# PWM.net
KiCad netlist of a schematic drawn in Altium Designer
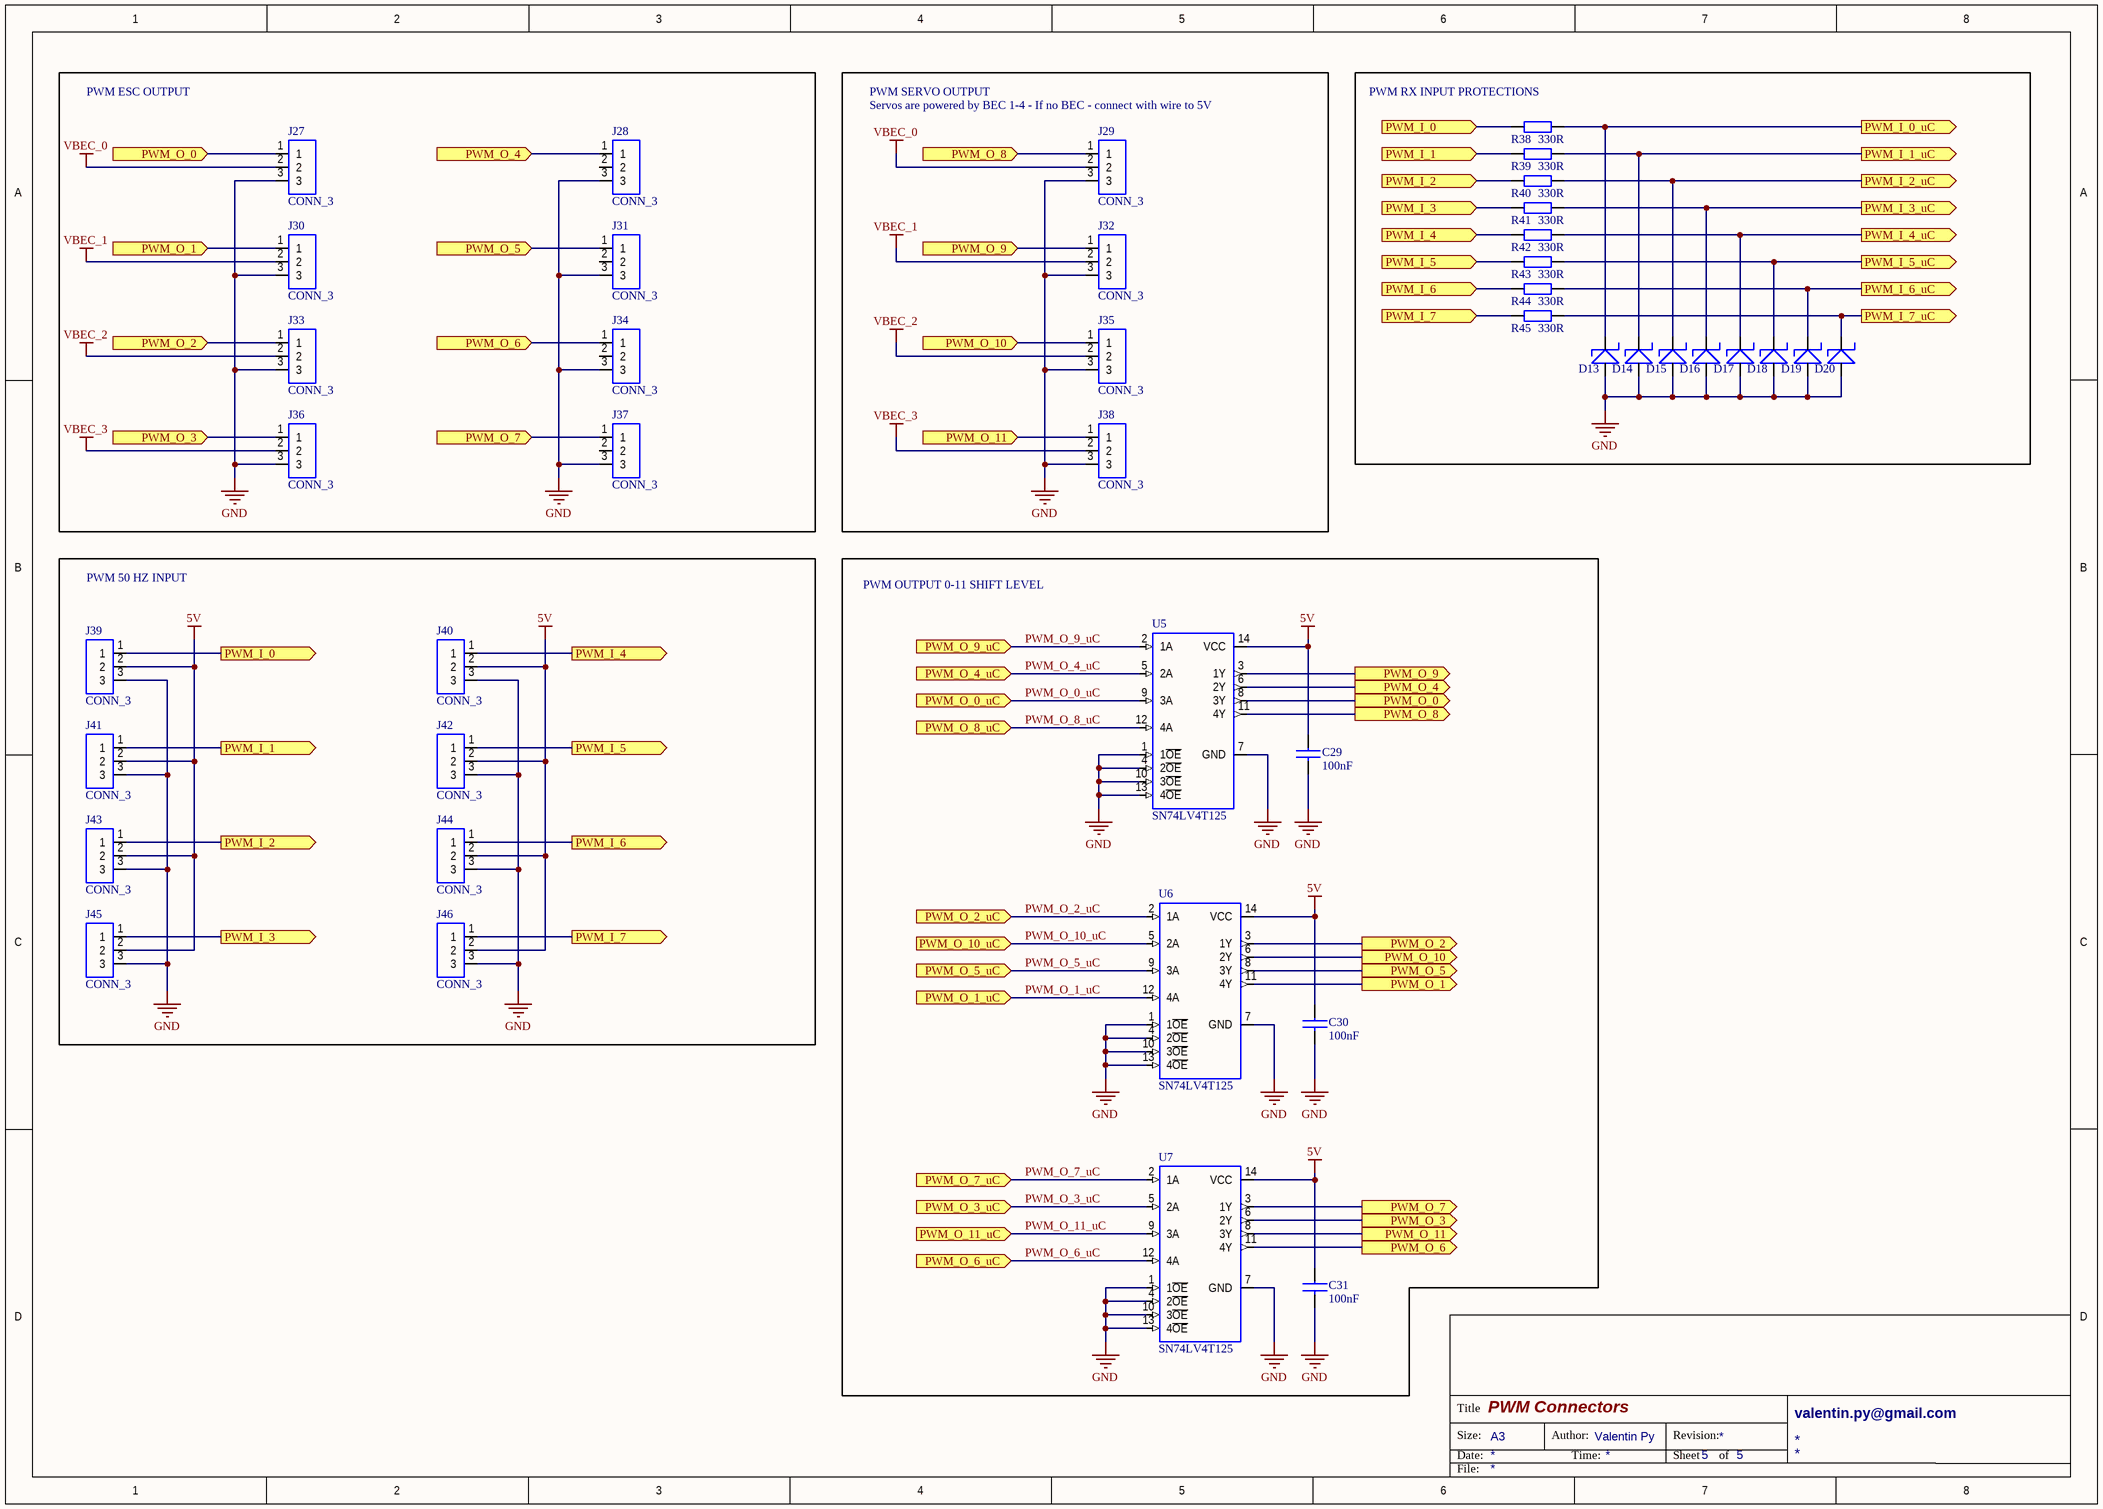
[diagram p0: PWM.SchDoc]

(export (version "E")
  (design (tool "Eeschema 10.0.6"))
  (components
    (comp (ref "C29")
      (value "100nF")
      (footprint "080503")
      (description "CAP CER 0.1UF 25V 10% X7R 0805")
      (libsource (lib "EISI") (part "CAPA"))
    )
    (comp (ref "C30")
      (value "100nF")
      (footprint "080503")
      (description "CAP CER 0.1UF 25V 10% X7R 0805")
      (libsource (lib "EISI") (part "CAPA"))
    )
    (comp (ref "C31")
      (value "100nF")
      (footprint "080503")
      (description "CAP CER 0.1UF 25V 10% X7R 0805")
      (libsource (lib "EISI") (part "CAPA"))
    )
    (comp (ref "D13")
      (value "TVS DIODE 3.3V")
      (footprint "SOD-523")
      (description "TVS DIODE 3.3VWM 8VC SOD523")
      (libsource (lib "PalIncTest") (part "Zener"))
    )
    (comp (ref "D14")
      (value "TVS DIODE 3.3V")
      (footprint "SOD-523")
      (description "TVS DIODE 3.3VWM 8VC SOD523")
      (libsource (lib "PalIncTest") (part "Zener"))
    )
    (comp (ref "D15")
      (value "TVS DIODE 3.3V")
      (footprint "SOD-523")
      (description "TVS DIODE 3.3VWM 8VC SOD523")
      (libsource (lib "PalIncTest") (part "Zener"))
    )
    (comp (ref "D16")
      (value "TVS DIODE 3.3V")
      (footprint "SOD-523")
      (description "TVS DIODE 3.3VWM 8VC SOD523")
      (libsource (lib "PalIncTest") (part "Zener"))
    )
    (comp (ref "D17")
      (value "TVS DIODE 3.3V")
      (footprint "SOD-523")
      (description "TVS DIODE 3.3VWM 8VC SOD523")
      (libsource (lib "PalIncTest") (part "Zener"))
    )
    (comp (ref "D18")
      (value "TVS DIODE 3.3V")
      (footprint "SOD-523")
      (description "TVS DIODE 3.3VWM 8VC SOD523")
      (libsource (lib "PalIncTest") (part "Zener"))
    )
    (comp (ref "D19")
      (value "TVS DIODE 3.3V")
      (footprint "SOD-523")
      (description "TVS DIODE 3.3VWM 8VC SOD523")
      (libsource (lib "PalIncTest") (part "Zener"))
    )
    (comp (ref "D20")
      (value "TVS DIODE 3.3V")
      (footprint "SOD-523")
      (description "TVS DIODE 3.3VWM 8VC SOD523")
      (libsource (lib "PalIncTest") (part "Zener"))
    )
    (comp (ref "J27")
      (value "CONN_3")
      (footprint "640454-3")
      (description "CONN HEADER 2.54mm 3")
      (libsource (lib "Aeroval") (part "CONN_3"))
    )
    (comp (ref "J28")
      (value "CONN_3")
      (footprint "640454-3")
      (description "CONN HEADER 2.54mm 3")
      (libsource (lib "Aeroval") (part "CONN_3"))
    )
    (comp (ref "J29")
      (value "CONN_3")
      (footprint "640454-3")
      (description "CONN HEADER 2.54mm 3")
      (libsource (lib "Aeroval") (part "CONN_3"))
    )
    (comp (ref "J30")
      (value "CONN_3")
      (footprint "640454-3")
      (description "CONN HEADER 2.54mm 3")
      (libsource (lib "Aeroval") (part "CONN_3"))
    )
    (comp (ref "J31")
      (value "CONN_3")
      (footprint "640454-3")
      (description "CONN HEADER 2.54mm 3")
      (libsource (lib "Aeroval") (part "CONN_3"))
    )
    (comp (ref "J32")
      (value "CONN_3")
      (footprint "640454-3")
      (description "CONN HEADER 2.54mm 3")
      (libsource (lib "Aeroval") (part "CONN_3"))
    )
    (comp (ref "J33")
      (value "CONN_3")
      (footprint "640454-3")
      (description "CONN HEADER 2.54mm 3")
      (libsource (lib "Aeroval") (part "CONN_3"))
    )
    (comp (ref "J34")
      (value "CONN_3")
      (footprint "640454-3")
      (description "CONN HEADER 2.54mm 3")
      (libsource (lib "Aeroval") (part "CONN_3"))
    )
    (comp (ref "J35")
      (value "CONN_3")
      (footprint "640454-3")
      (description "CONN HEADER 2.54mm 3")
      (libsource (lib "Aeroval") (part "CONN_3"))
    )
    (comp (ref "J36")
      (value "CONN_3")
      (footprint "640454-3")
      (description "CONN HEADER 2.54mm 3")
      (libsource (lib "Aeroval") (part "CONN_3"))
    )
    (comp (ref "J37")
      (value "CONN_3")
      (footprint "640454-3")
      (description "CONN HEADER 2.54mm 3")
      (libsource (lib "Aeroval") (part "CONN_3"))
    )
    (comp (ref "J38")
      (value "CONN_3")
      (footprint "640454-3")
      (description "CONN HEADER 2.54mm 3")
      (libsource (lib "Aeroval") (part "CONN_3"))
    )
    (comp (ref "J39")
      (value "CONN_3")
      (footprint "640454-3")
      (description "CONN HEADER 2.54mm 3")
      (libsource (lib "Aeroval") (part "CONN_3"))
    )
    (comp (ref "J40")
      (value "CONN_3")
      (footprint "640454-3")
      (description "CONN HEADER 2.54mm 3")
      (libsource (lib "Aeroval") (part "CONN_3"))
    )
    (comp (ref "J41")
      (value "CONN_3")
      (footprint "640454-3")
      (description "CONN HEADER 2.54mm 3")
      (libsource (lib "Aeroval") (part "CONN_3"))
    )
    (comp (ref "J42")
      (value "CONN_3")
      (footprint "640454-3")
      (description "CONN HEADER 2.54mm 3")
      (libsource (lib "Aeroval") (part "CONN_3"))
    )
    (comp (ref "J43")
      (value "CONN_3")
      (footprint "640454-3")
      (description "CONN HEADER 2.54mm 3")
      (libsource (lib "Aeroval") (part "CONN_3"))
    )
    (comp (ref "J44")
      (value "CONN_3")
      (footprint "640454-3")
      (description "CONN HEADER 2.54mm 3")
      (libsource (lib "Aeroval") (part "CONN_3"))
    )
    (comp (ref "J45")
      (value "CONN_3")
      (footprint "640454-3")
      (description "CONN HEADER 2.54mm 3")
      (libsource (lib "Aeroval") (part "CONN_3"))
    )
    (comp (ref "J46")
      (value "CONN_3")
      (footprint "640454-3")
      (description "CONN HEADER 2.54mm 3")
      (libsource (lib "Aeroval") (part "CONN_3"))
    )
    (comp (ref "R38")
      (value "330R")
      (footprint "060301")
      (description "RES 330R 0805")
      (libsource (lib "EISI") (part "RES"))
    )
    (comp (ref "R39")
      (value "330R")
      (footprint "060301")
      (description "RES 330R 0805")
      (libsource (lib "EISI") (part "RES"))
    )
    (comp (ref "R40")
      (value "330R")
      (footprint "060301")
      (description "RES 330R 0805")
      (libsource (lib "EISI") (part "RES"))
    )
    (comp (ref "R41")
      (value "330R")
      (footprint "060301")
      (description "RES 330R 0805")
      (libsource (lib "EISI") (part "RES"))
    )
    (comp (ref "R42")
      (value "330R")
      (footprint "060301")
      (description "RES 330R 0805")
      (libsource (lib "EISI") (part "RES"))
    )
    (comp (ref "R43")
      (value "330R")
      (footprint "060301")
      (description "RES 330R 0805")
      (libsource (lib "EISI") (part "RES"))
    )
    (comp (ref "R44")
      (value "330R")
      (footprint "060301")
      (description "RES 330R 0805")
      (libsource (lib "EISI") (part "RES"))
    )
    (comp (ref "R45")
      (value "330R")
      (footprint "060301")
      (description "RES 330R 0805")
      (libsource (lib "EISI") (part "RES"))
    )
    (comp (ref "U5")
      (value "SN74LV4T125")
      (footprint "TSSOP14")
      (description "IC BUFF/DVR NON-INVERT 14TSSOP")
      (libsource (lib "Aeroval") (part "SN74LV4T125"))
    )
    (comp (ref "U6")
      (value "SN74LV4T125")
      (footprint "TSSOP14")
      (description "IC BUFF/DVR NON-INVERT 14TSSOP")
      (libsource (lib "Aeroval") (part "SN74LV4T125"))
    )
    (comp (ref "U7")
      (value "SN74LV4T125")
      (footprint "TSSOP14")
      (description "IC BUFF/DVR NON-INVERT 14TSSOP")
      (libsource (lib "Aeroval") (part "SN74LV4T125"))
    )
  )
  (nets
    (net (code "1") (name "/PWM_I_0") (class "Default")
      (node (ref "J39") (pin "1") (pinfunction "1_1") (pintype "bidirectional"))
      (node (ref "R38") (pin "2") (pinfunction "2_2") (pintype "passive"))
    )
    (net (code "2") (name "/PWM_I_0_uC") (class "Default")
      (node (ref "D13") (pin "2") (pinfunction "2_2") (pintype "power_in"))
      (node (ref "R38") (pin "1") (pinfunction "1_1") (pintype "passive"))
    )
    (net (code "3") (name "/PWM_I_1") (class "Default")
      (node (ref "J41") (pin "1") (pinfunction "1_1") (pintype "bidirectional"))
      (node (ref "R39") (pin "2") (pinfunction "2_2") (pintype "passive"))
    )
    (net (code "4") (name "/PWM_I_1_uC") (class "Default")
      (node (ref "D14") (pin "2") (pinfunction "2_2") (pintype "power_in"))
      (node (ref "R39") (pin "1") (pinfunction "1_1") (pintype "passive"))
    )
    (net (code "5") (name "/PWM_I_2") (class "Default")
      (node (ref "J43") (pin "1") (pinfunction "1_1") (pintype "bidirectional"))
      (node (ref "R40") (pin "2") (pinfunction "2_2") (pintype "passive"))
    )
    (net (code "6") (name "/PWM_I_2_uC") (class "Default")
      (node (ref "D15") (pin "2") (pinfunction "2_2") (pintype "power_in"))
      (node (ref "R40") (pin "1") (pinfunction "1_1") (pintype "passive"))
    )
    (net (code "7") (name "/PWM_I_3") (class "Default")
      (node (ref "J45") (pin "1") (pinfunction "1_1") (pintype "bidirectional"))
      (node (ref "R41") (pin "2") (pinfunction "2_2") (pintype "passive"))
    )
    (net (code "8") (name "/PWM_I_3_uC") (class "Default")
      (node (ref "D16") (pin "2") (pinfunction "2_2") (pintype "power_in"))
      (node (ref "R41") (pin "1") (pinfunction "1_1") (pintype "passive"))
    )
    (net (code "9") (name "/PWM_I_4") (class "Default")
      (node (ref "J40") (pin "1") (pinfunction "1_1") (pintype "bidirectional"))
      (node (ref "R42") (pin "2") (pinfunction "2_2") (pintype "passive"))
    )
    (net (code "10") (name "/PWM_I_4_uC") (class "Default")
      (node (ref "D17") (pin "2") (pinfunction "2_2") (pintype "power_in"))
      (node (ref "R42") (pin "1") (pinfunction "1_1") (pintype "passive"))
    )
    (net (code "11") (name "/PWM_I_5") (class "Default")
      (node (ref "J42") (pin "1") (pinfunction "1_1") (pintype "bidirectional"))
      (node (ref "R43") (pin "2") (pinfunction "2_2") (pintype "passive"))
    )
    (net (code "12") (name "/PWM_I_5_uC") (class "Default")
      (node (ref "D18") (pin "2") (pinfunction "2_2") (pintype "power_in"))
      (node (ref "R43") (pin "1") (pinfunction "1_1") (pintype "passive"))
    )
    (net (code "13") (name "/PWM_I_6") (class "Default")
      (node (ref "J44") (pin "1") (pinfunction "1_1") (pintype "bidirectional"))
      (node (ref "R44") (pin "2") (pinfunction "2_2") (pintype "passive"))
    )
    (net (code "14") (name "/PWM_I_6_uC") (class "Default")
      (node (ref "D19") (pin "2") (pinfunction "2_2") (pintype "power_in"))
      (node (ref "R44") (pin "1") (pinfunction "1_1") (pintype "passive"))
    )
    (net (code "15") (name "/PWM_I_7") (class "Default")
      (node (ref "J46") (pin "1") (pinfunction "1_1") (pintype "bidirectional"))
      (node (ref "R45") (pin "2") (pinfunction "2_2") (pintype "passive"))
    )
    (net (code "16") (name "/PWM_I_7_uC") (class "Default")
      (node (ref "D20") (pin "2") (pinfunction "2_2") (pintype "power_in"))
      (node (ref "R45") (pin "1") (pinfunction "1_1") (pintype "passive"))
    )
    (net (code "17") (name "/PWM_O_0") (class "Default")
      (node (ref "J27") (pin "1") (pinfunction "1_1") (pintype "bidirectional"))
      (node (ref "U5") (pin "8") (pinfunction "3Y_8") (pintype "output"))
    )
    (net (code "18") (name "/PWM_O_0_uC") (class "Default")
      (node (ref "U5") (pin "9") (pinfunction "3A_9") (pintype "input"))
    )
    (net (code "19") (name "/PWM_O_1") (class "Default")
      (node (ref "J30") (pin "1") (pinfunction "1_1") (pintype "bidirectional"))
      (node (ref "U6") (pin "11") (pinfunction "4Y_11") (pintype "output"))
    )
    (net (code "20") (name "/PWM_O_1_uC") (class "Default")
      (node (ref "U6") (pin "12") (pinfunction "4A_12") (pintype "input"))
    )
    (net (code "21") (name "/PWM_O_2") (class "Default")
      (node (ref "J33") (pin "1") (pinfunction "1_1") (pintype "bidirectional"))
      (node (ref "U6") (pin "3") (pinfunction "1Y_3") (pintype "output"))
    )
    (net (code "22") (name "/PWM_O_2_uC") (class "Default")
      (node (ref "U6") (pin "2") (pinfunction "1A_2") (pintype "input"))
    )
    (net (code "23") (name "/PWM_O_3") (class "Default")
      (node (ref "J36") (pin "1") (pinfunction "1_1") (pintype "bidirectional"))
      (node (ref "U7") (pin "6") (pinfunction "2Y_6") (pintype "output"))
    )
    (net (code "24") (name "/PWM_O_3_uC") (class "Default")
      (node (ref "U7") (pin "5") (pinfunction "2A_5") (pintype "input"))
    )
    (net (code "25") (name "/PWM_O_4") (class "Default")
      (node (ref "J28") (pin "1") (pinfunction "1_1") (pintype "bidirectional"))
      (node (ref "U5") (pin "6") (pinfunction "2Y_6") (pintype "output"))
    )
    (net (code "26") (name "/PWM_O_4_uC") (class "Default")
      (node (ref "U5") (pin "5") (pinfunction "2A_5") (pintype "input"))
    )
    (net (code "27") (name "/PWM_O_5") (class "Default")
      (node (ref "J31") (pin "1") (pinfunction "1_1") (pintype "bidirectional"))
      (node (ref "U6") (pin "8") (pinfunction "3Y_8") (pintype "output"))
    )
    (net (code "28") (name "/PWM_O_5_uC") (class "Default")
      (node (ref "U6") (pin "9") (pinfunction "3A_9") (pintype "input"))
    )
    (net (code "29") (name "/PWM_O_6") (class "Default")
      (node (ref "J34") (pin "1") (pinfunction "1_1") (pintype "bidirectional"))
      (node (ref "U7") (pin "11") (pinfunction "4Y_11") (pintype "output"))
    )
    (net (code "30") (name "/PWM_O_6_uC") (class "Default")
      (node (ref "U7") (pin "12") (pinfunction "4A_12") (pintype "input"))
    )
    (net (code "31") (name "/PWM_O_7") (class "Default")
      (node (ref "J37") (pin "1") (pinfunction "1_1") (pintype "bidirectional"))
      (node (ref "U7") (pin "3") (pinfunction "1Y_3") (pintype "output"))
    )
    (net (code "32") (name "/PWM_O_7_uC") (class "Default")
      (node (ref "U7") (pin "2") (pinfunction "1A_2") (pintype "input"))
    )
    (net (code "33") (name "/PWM_O_8") (class "Default")
      (node (ref "J29") (pin "1") (pinfunction "1_1") (pintype "bidirectional"))
      (node (ref "U5") (pin "11") (pinfunction "4Y_11") (pintype "output"))
    )
    (net (code "34") (name "/PWM_O_8_uC") (class "Default")
      (node (ref "U5") (pin "12") (pinfunction "4A_12") (pintype "input"))
    )
    (net (code "35") (name "/PWM_O_9") (class "Default")
      (node (ref "J32") (pin "1") (pinfunction "1_1") (pintype "bidirectional"))
      (node (ref "U5") (pin "3") (pinfunction "1Y_3") (pintype "output"))
    )
    (net (code "36") (name "/PWM_O_9_uC") (class "Default")
      (node (ref "U5") (pin "2") (pinfunction "1A_2") (pintype "input"))
    )
    (net (code "37") (name "/PWM_O_10") (class "Default")
      (node (ref "J35") (pin "1") (pinfunction "1_1") (pintype "bidirectional"))
      (node (ref "U6") (pin "6") (pinfunction "2Y_6") (pintype "output"))
    )
    (net (code "38") (name "/PWM_O_10_uC") (class "Default")
      (node (ref "U6") (pin "5") (pinfunction "2A_5") (pintype "input"))
    )
    (net (code "39") (name "/PWM_O_11") (class "Default")
      (node (ref "J38") (pin "1") (pinfunction "1_1") (pintype "bidirectional"))
      (node (ref "U7") (pin "8") (pinfunction "3Y_8") (pintype "output"))
    )
    (net (code "40") (name "/PWM_O_11_uC") (class "Default")
      (node (ref "U7") (pin "9") (pinfunction "3A_9") (pintype "input"))
    )
    (net (code "41") (name "5V") (class "Default")
      (node (ref "C29") (pin "1") (pinfunction "1_1") (pintype "passive"))
      (node (ref "C30") (pin "1") (pinfunction "1_1") (pintype "passive"))
      (node (ref "C31") (pin "1") (pinfunction "1_1") (pintype "passive"))
      (node (ref "J39") (pin "2") (pinfunction "2_2") (pintype "bidirectional"))
      (node (ref "J40") (pin "2") (pinfunction "2_2") (pintype "bidirectional"))
      (node (ref "J41") (pin "2") (pinfunction "2_2") (pintype "bidirectional"))
      (node (ref "J42") (pin "2") (pinfunction "2_2") (pintype "bidirectional"))
      (node (ref "J43") (pin "2") (pinfunction "2_2") (pintype "bidirectional"))
      (node (ref "J44") (pin "2") (pinfunction "2_2") (pintype "bidirectional"))
      (node (ref "J45") (pin "2") (pinfunction "2_2") (pintype "bidirectional"))
      (node (ref "J46") (pin "2") (pinfunction "2_2") (pintype "bidirectional"))
      (node (ref "U5") (pin "14") (pinfunction "VCC_14") (pintype "power_in"))
      (node (ref "U6") (pin "14") (pinfunction "VCC_14") (pintype "power_in"))
      (node (ref "U7") (pin "14") (pinfunction "VCC_14") (pintype "power_in"))
    )
    (net (code "42") (name "GND") (class "Default")
      (node (ref "C29") (pin "2") (pinfunction "2_2") (pintype "passive"))
      (node (ref "C30") (pin "2") (pinfunction "2_2") (pintype "passive"))
      (node (ref "C31") (pin "2") (pinfunction "2_2") (pintype "passive"))
      (node (ref "D13") (pin "1") (pinfunction "1_1") (pintype "power_in"))
      (node (ref "D14") (pin "1") (pinfunction "1_1") (pintype "power_in"))
      (node (ref "D15") (pin "1") (pinfunction "1_1") (pintype "power_in"))
      (node (ref "D16") (pin "1") (pinfunction "1_1") (pintype "power_in"))
      (node (ref "D17") (pin "1") (pinfunction "1_1") (pintype "power_in"))
      (node (ref "D18") (pin "1") (pinfunction "1_1") (pintype "power_in"))
      (node (ref "D19") (pin "1") (pinfunction "1_1") (pintype "power_in"))
      (node (ref "D20") (pin "1") (pinfunction "1_1") (pintype "power_in"))
      (node (ref "J27") (pin "3") (pinfunction "3_3") (pintype "bidirectional"))
      (node (ref "J28") (pin "3") (pinfunction "3_3") (pintype "bidirectional"))
      (node (ref "J29") (pin "3") (pinfunction "3_3") (pintype "bidirectional"))
      (node (ref "J30") (pin "3") (pinfunction "3_3") (pintype "bidirectional"))
      (node (ref "J31") (pin "3") (pinfunction "3_3") (pintype "bidirectional"))
      (node (ref "J32") (pin "3") (pinfunction "3_3") (pintype "bidirectional"))
      (node (ref "J33") (pin "3") (pinfunction "3_3") (pintype "bidirectional"))
      (node (ref "J34") (pin "3") (pinfunction "3_3") (pintype "bidirectional"))
      (node (ref "J35") (pin "3") (pinfunction "3_3") (pintype "bidirectional"))
      (node (ref "J36") (pin "3") (pinfunction "3_3") (pintype "bidirectional"))
      (node (ref "J37") (pin "3") (pinfunction "3_3") (pintype "bidirectional"))
      (node (ref "J38") (pin "3") (pinfunction "3_3") (pintype "bidirectional"))
      (node (ref "J39") (pin "3") (pinfunction "3_3") (pintype "bidirectional"))
      (node (ref "J40") (pin "3") (pinfunction "3_3") (pintype "bidirectional"))
      (node (ref "J41") (pin "3") (pinfunction "3_3") (pintype "bidirectional"))
      (node (ref "J42") (pin "3") (pinfunction "3_3") (pintype "bidirectional"))
      (node (ref "J43") (pin "3") (pinfunction "3_3") (pintype "bidirectional"))
      (node (ref "J44") (pin "3") (pinfunction "3_3") (pintype "bidirectional"))
      (node (ref "J45") (pin "3") (pinfunction "3_3") (pintype "bidirectional"))
      (node (ref "J46") (pin "3") (pinfunction "3_3") (pintype "bidirectional"))
      (node (ref "U5") (pin "1") (pinfunction "1~{OE}_1") (pintype "input"))
      (node (ref "U5") (pin "10") (pinfunction "3~{OE}_10") (pintype "input"))
      (node (ref "U5") (pin "13") (pinfunction "4~{OE}_13") (pintype "input"))
      (node (ref "U5") (pin "4") (pinfunction "2~{OE}_4") (pintype "input"))
      (node (ref "U5") (pin "7") (pinfunction "GND_7") (pintype "power_in"))
      (node (ref "U6") (pin "1") (pinfunction "1~{OE}_1") (pintype "input"))
      (node (ref "U6") (pin "10") (pinfunction "3~{OE}_10") (pintype "input"))
      (node (ref "U6") (pin "13") (pinfunction "4~{OE}_13") (pintype "input"))
      (node (ref "U6") (pin "4") (pinfunction "2~{OE}_4") (pintype "input"))
      (node (ref "U6") (pin "7") (pinfunction "GND_7") (pintype "power_in"))
      (node (ref "U7") (pin "1") (pinfunction "1~{OE}_1") (pintype "input"))
      (node (ref "U7") (pin "10") (pinfunction "3~{OE}_10") (pintype "input"))
      (node (ref "U7") (pin "13") (pinfunction "4~{OE}_13") (pintype "input"))
      (node (ref "U7") (pin "4") (pinfunction "2~{OE}_4") (pintype "input"))
      (node (ref "U7") (pin "7") (pinfunction "GND_7") (pintype "power_in"))
    )
    (net (code "43") (name "VBEC_0") (class "Default")
      (node (ref "J27") (pin "2") (pinfunction "2_2") (pintype "bidirectional"))
      (node (ref "J29") (pin "2") (pinfunction "2_2") (pintype "bidirectional"))
    )
    (net (code "44") (name "VBEC_1") (class "Default")
      (node (ref "J30") (pin "2") (pinfunction "2_2") (pintype "bidirectional"))
      (node (ref "J32") (pin "2") (pinfunction "2_2") (pintype "bidirectional"))
    )
    (net (code "45") (name "VBEC_2") (class "Default")
      (node (ref "J33") (pin "2") (pinfunction "2_2") (pintype "bidirectional"))
      (node (ref "J35") (pin "2") (pinfunction "2_2") (pintype "bidirectional"))
    )
    (net (code "46") (name "VBEC_3") (class "Default")
      (node (ref "J36") (pin "2") (pinfunction "2_2") (pintype "bidirectional"))
      (node (ref "J38") (pin "2") (pinfunction "2_2") (pintype "bidirectional"))
    )
    (net (code "47") (name "unconnected-(J28-Pad2)") (class "Default")
      (node (ref "J28") (pin "2") (pinfunction "2_2") (pintype "bidirectional"))
    )
    (net (code "48") (name "unconnected-(J31-Pad2)") (class "Default")
      (node (ref "J31") (pin "2") (pinfunction "2_2") (pintype "bidirectional"))
    )
    (net (code "49") (name "unconnected-(J34-Pad2)") (class "Default")
      (node (ref "J34") (pin "2") (pinfunction "2_2") (pintype "bidirectional"))
    )
    (net (code "50") (name "unconnected-(J37-Pad2)") (class "Default")
      (node (ref "J37") (pin "2") (pinfunction "2_2") (pintype "bidirectional"))
    )
  )
)
